# spi-interface.net
KiCad netlist of a schematic drawn in EAGLE
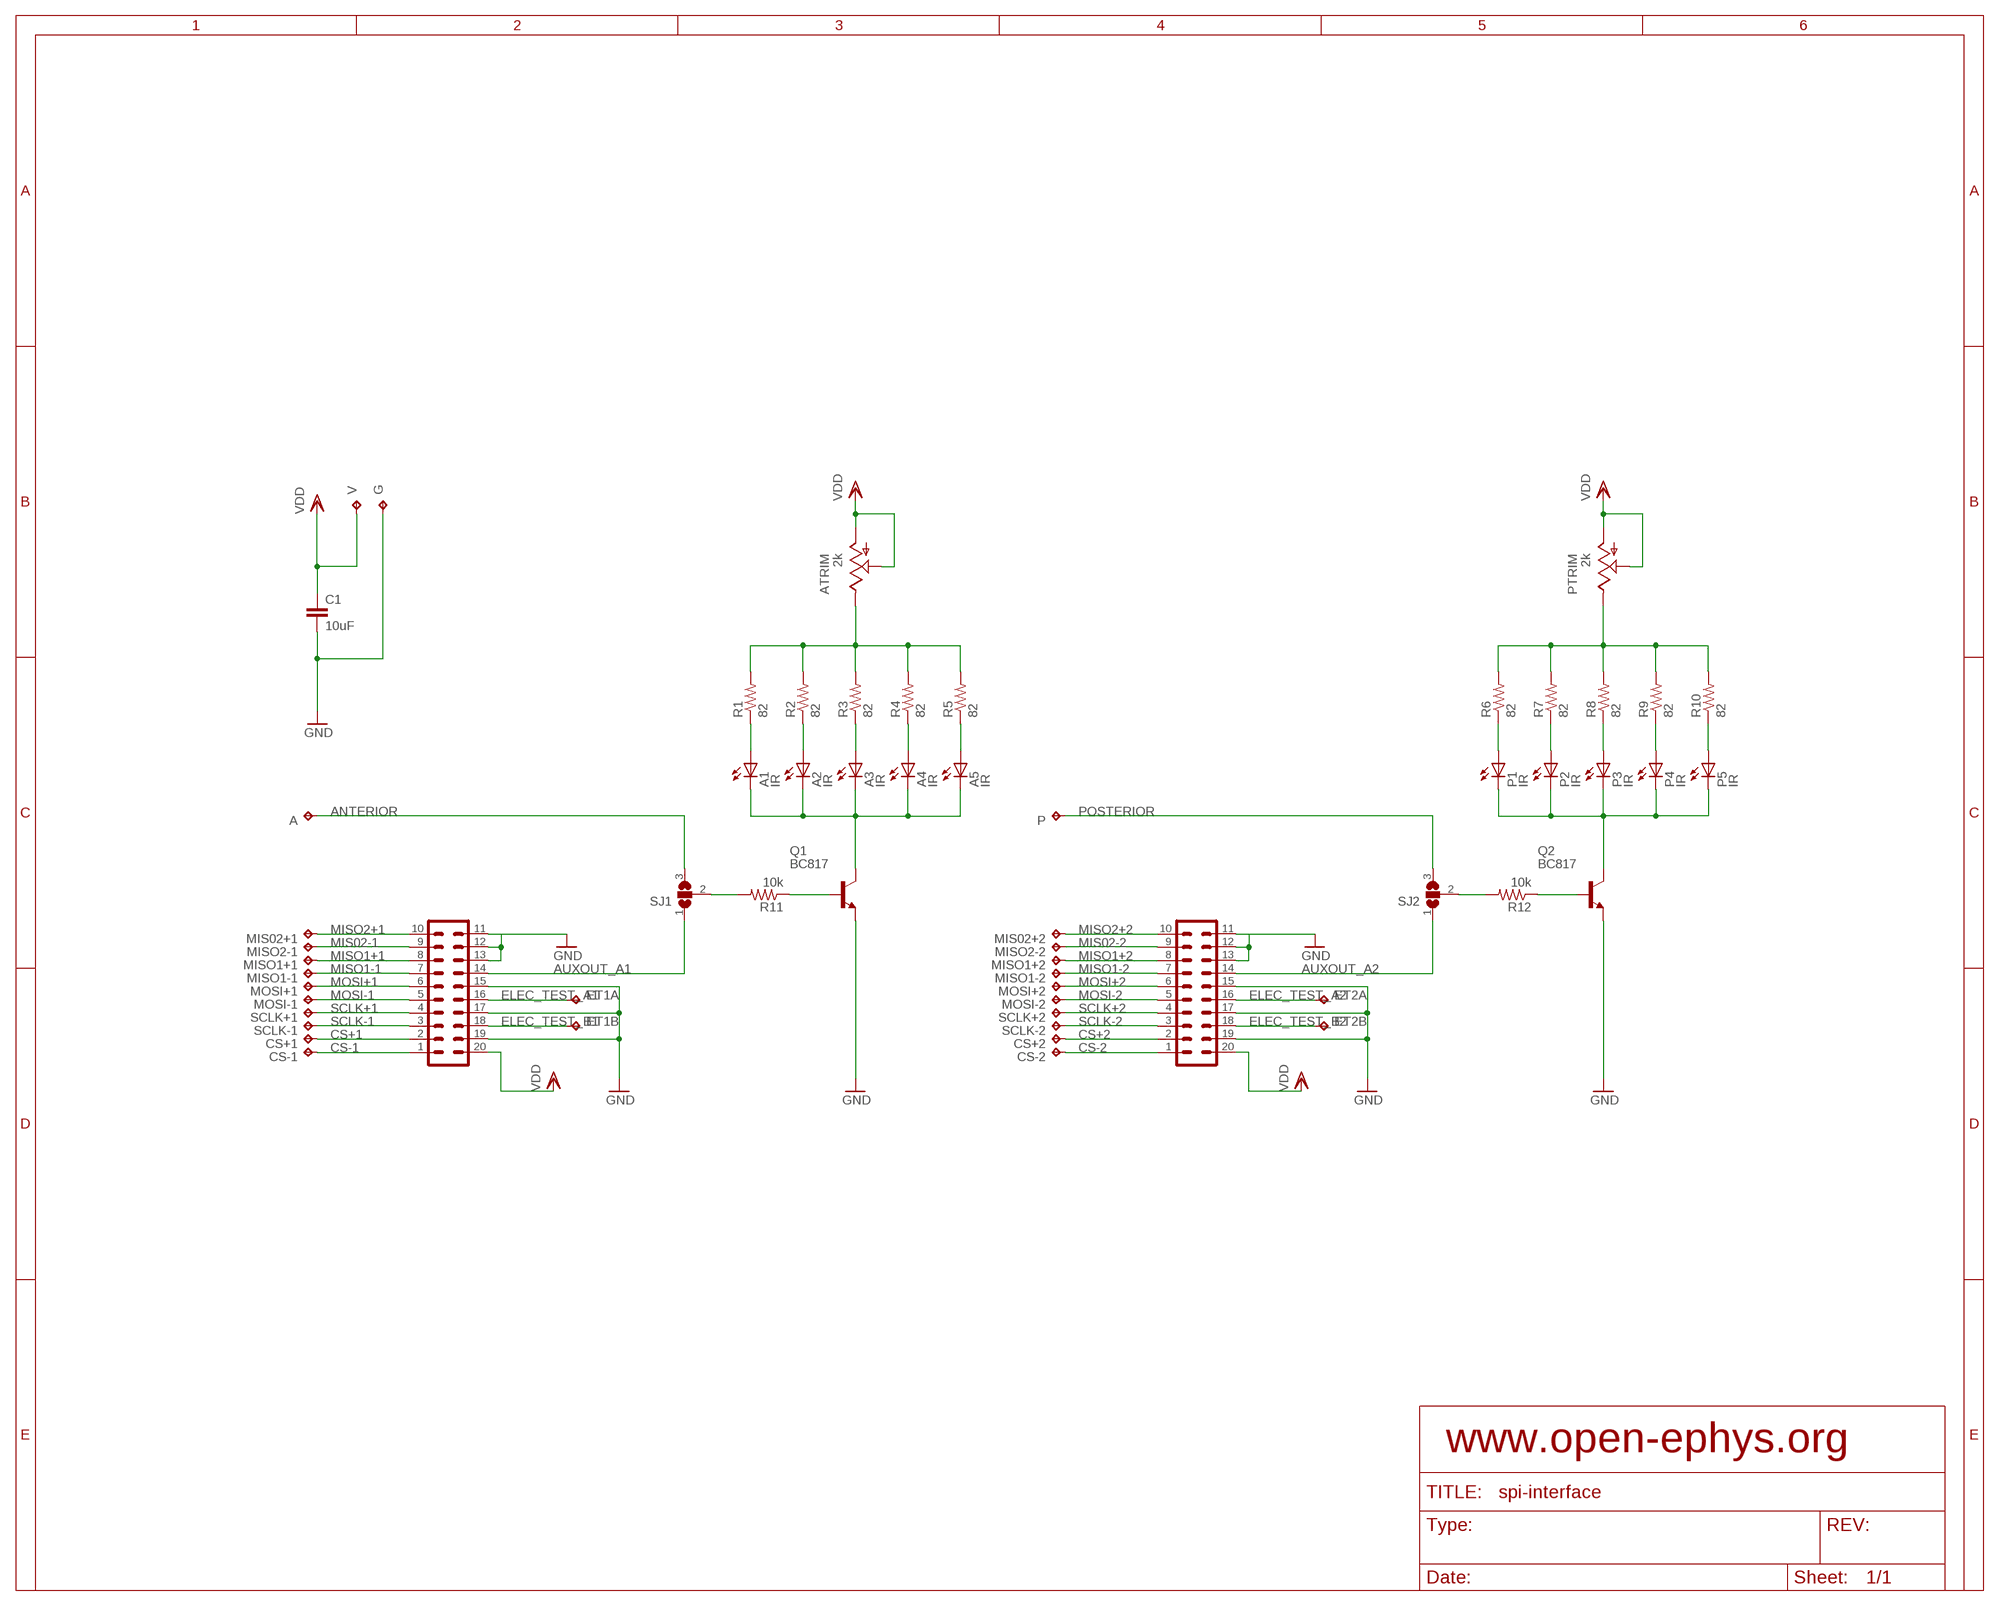
[diagram p0: schematic, sheet 1]

(export (version "E")
  (design (tool "Eeschema 10.0.6"))
  (components
    (comp (ref "A")
      (value "TP_01")
      (footprint "eagle-import:TP01")
      (libsource (lib "eagle-import") (part "TP_01"))
    )
    (comp (ref "A1")
      (value "IR")
      (footprint "eagle-import:LED-0603")
      (libsource (lib "eagle-import") (part "LED_0603"))
    )
    (comp (ref "A2")
      (value "IR")
      (footprint "eagle-import:LED-0603")
      (libsource (lib "eagle-import") (part "LED_0603"))
    )
    (comp (ref "A3")
      (value "IR")
      (footprint "eagle-import:LED-0603")
      (libsource (lib "eagle-import") (part "LED_0603"))
    )
    (comp (ref "A4")
      (value "IR")
      (footprint "eagle-import:LED-0603")
      (libsource (lib "eagle-import") (part "LED_0603"))
    )
    (comp (ref "A5")
      (value "IR")
      (footprint "eagle-import:LED-0603")
      (libsource (lib "eagle-import") (part "LED_0603"))
    )
    (comp (ref "ATRIM")
      (value "2k")
      (footprint "eagle-import:EIA_EIAJ")
      (libsource (lib "eagle-import") (part "TRIM_EIA/EIAJ"))
    )
    (comp (ref "C1")
      (value "10uF")
      (footprint "eagle-import:0805")
      (fields (field (name "PARTNO") "C2012X5R1Cxxxxxxx"))
      (libsource (lib "eagle-import") (part "C_0805"))
    )
    (comp (ref "CS+1")
      (value "TP_01")
      (footprint "eagle-import:TP01")
      (libsource (lib "eagle-import") (part "TP_01"))
    )
    (comp (ref "CS+2")
      (value "TP_01")
      (footprint "eagle-import:TP01")
      (libsource (lib "eagle-import") (part "TP_01"))
    )
    (comp (ref "CS-1")
      (value "TP_01")
      (footprint "eagle-import:TP01")
      (libsource (lib "eagle-import") (part "TP_01"))
    )
    (comp (ref "CS-2")
      (value "TP_01")
      (footprint "eagle-import:TP01")
      (libsource (lib "eagle-import") (part "TP_01"))
    )
    (comp (ref "ET1A")
      (value "TP_03")
      (footprint "eagle-import:TP03")
      (libsource (lib "eagle-import") (part "TP_03"))
    )
    (comp (ref "ET1B")
      (value "TP_03")
      (footprint "eagle-import:TP03")
      (libsource (lib "eagle-import") (part "TP_03"))
    )
    (comp (ref "ET2A")
      (value "TP_03")
      (footprint "eagle-import:TP03")
      (libsource (lib "eagle-import") (part "TP_03"))
    )
    (comp (ref "ET2B")
      (value "TP_03")
      (footprint "eagle-import:TP03")
      (libsource (lib "eagle-import") (part "TP_03"))
    )
    (comp (ref "G")
      (value "TP_02")
      (footprint "eagle-import:TP02")
      (libsource (lib "eagle-import") (part "TP_02"))
    )
    (comp (ref "HS1")
      (value "JMD20-V")
      (footprint "eagle-import:JMD20-V")
      (libsource (lib "eagle-import") (part "PINHD-2X10_JMD20-V"))
    )
    (comp (ref "HS2")
      (value "JMD20-V")
      (footprint "eagle-import:JMD20-V")
      (libsource (lib "eagle-import") (part "PINHD-2X10_JMD20-V"))
    )
    (comp (ref "MIS02+1")
      (value "TP_01")
      (footprint "eagle-import:TP01")
      (libsource (lib "eagle-import") (part "TP_01"))
    )
    (comp (ref "MIS02+2")
      (value "TP_01")
      (footprint "eagle-import:TP01")
      (libsource (lib "eagle-import") (part "TP_01"))
    )
    (comp (ref "MISO1+1")
      (value "TP_01")
      (footprint "eagle-import:TP01")
      (libsource (lib "eagle-import") (part "TP_01"))
    )
    (comp (ref "MISO1+2")
      (value "TP_01")
      (footprint "eagle-import:TP01")
      (libsource (lib "eagle-import") (part "TP_01"))
    )
    (comp (ref "MISO1-1")
      (value "TP_01")
      (footprint "eagle-import:TP01")
      (libsource (lib "eagle-import") (part "TP_01"))
    )
    (comp (ref "MISO1-2")
      (value "TP_01")
      (footprint "eagle-import:TP01")
      (libsource (lib "eagle-import") (part "TP_01"))
    )
    (comp (ref "MISO2-1")
      (value "TP_01")
      (footprint "eagle-import:TP01")
      (libsource (lib "eagle-import") (part "TP_01"))
    )
    (comp (ref "MISO2-2")
      (value "TP_01")
      (footprint "eagle-import:TP01")
      (libsource (lib "eagle-import") (part "TP_01"))
    )
    (comp (ref "MOSI+1")
      (value "TP_01")
      (footprint "eagle-import:TP01")
      (libsource (lib "eagle-import") (part "TP_01"))
    )
    (comp (ref "MOSI+2")
      (value "TP_01")
      (footprint "eagle-import:TP01")
      (libsource (lib "eagle-import") (part "TP_01"))
    )
    (comp (ref "MOSI-1")
      (value "TP_01")
      (footprint "eagle-import:TP01")
      (libsource (lib "eagle-import") (part "TP_01"))
    )
    (comp (ref "MOSI-2")
      (value "TP_01")
      (footprint "eagle-import:TP01")
      (libsource (lib "eagle-import") (part "TP_01"))
    )
    (comp (ref "P")
      (value "TP_01")
      (footprint "eagle-import:TP01")
      (libsource (lib "eagle-import") (part "TP_01"))
    )
    (comp (ref "P1")
      (value "IR")
      (footprint "eagle-import:LED-0603")
      (libsource (lib "eagle-import") (part "LED_0603"))
    )
    (comp (ref "P2")
      (value "IR")
      (footprint "eagle-import:LED-0603")
      (libsource (lib "eagle-import") (part "LED_0603"))
    )
    (comp (ref "P3")
      (value "IR")
      (footprint "eagle-import:LED-0603")
      (libsource (lib "eagle-import") (part "LED_0603"))
    )
    (comp (ref "P4")
      (value "IR")
      (footprint "eagle-import:LED-0603")
      (libsource (lib "eagle-import") (part "LED_0603"))
    )
    (comp (ref "P5")
      (value "IR")
      (footprint "eagle-import:LED-0603")
      (libsource (lib "eagle-import") (part "LED_0603"))
    )
    (comp (ref "PTRIM")
      (value "2k")
      (footprint "eagle-import:EIA_EIAJ")
      (libsource (lib "eagle-import") (part "TRIM_EIA/EIAJ"))
    )
    (comp (ref "Q1")
      (value "BC817")
      (footprint "eagle-import:SOT23-BEC")
      (libsource (lib "eagle-import") (part "BC817SMD-16"))
    )
    (comp (ref "Q2")
      (value "BC817")
      (footprint "eagle-import:SOT23-BEC")
      (libsource (lib "eagle-import") (part "BC817SMD-16"))
    )
    (comp (ref "R1")
      (value "82")
      (footprint "eagle-import:0402")
      (libsource (lib "eagle-import") (part "R_0402"))
    )
    (comp (ref "R2")
      (value "82")
      (footprint "eagle-import:0402")
      (libsource (lib "eagle-import") (part "R_0402"))
    )
    (comp (ref "R3")
      (value "82")
      (footprint "eagle-import:0402")
      (libsource (lib "eagle-import") (part "R_0402"))
    )
    (comp (ref "R4")
      (value "82")
      (footprint "eagle-import:0402")
      (libsource (lib "eagle-import") (part "R_0402"))
    )
    (comp (ref "R5")
      (value "82")
      (footprint "eagle-import:0402")
      (libsource (lib "eagle-import") (part "R_0402"))
    )
    (comp (ref "R6")
      (value "82")
      (footprint "eagle-import:0402")
      (libsource (lib "eagle-import") (part "R_0402"))
    )
    (comp (ref "R7")
      (value "82")
      (footprint "eagle-import:0402")
      (libsource (lib "eagle-import") (part "R_0402"))
    )
    (comp (ref "R8")
      (value "82")
      (footprint "eagle-import:0402")
      (libsource (lib "eagle-import") (part "R_0402"))
    )
    (comp (ref "R9")
      (value "82")
      (footprint "eagle-import:0402")
      (libsource (lib "eagle-import") (part "R_0402"))
    )
    (comp (ref "R10")
      (value "82")
      (footprint "eagle-import:0402")
      (libsource (lib "eagle-import") (part "R_0402"))
    )
    (comp (ref "R11")
      (value "10k")
      (footprint "eagle-import:0402")
      (libsource (lib "eagle-import") (part "R_0402"))
    )
    (comp (ref "R12")
      (value "10k")
      (footprint "eagle-import:0402")
      (libsource (lib "eagle-import") (part "R_0402"))
    )
    (comp (ref "SCLK+1")
      (value "TP_01")
      (footprint "eagle-import:TP01")
      (libsource (lib "eagle-import") (part "TP_01"))
    )
    (comp (ref "SCLK+2")
      (value "TP_01")
      (footprint "eagle-import:TP01")
      (libsource (lib "eagle-import") (part "TP_01"))
    )
    (comp (ref "SCLK-1")
      (value "TP_01")
      (footprint "eagle-import:TP01")
      (libsource (lib "eagle-import") (part "TP_01"))
    )
    (comp (ref "SCLK-2")
      (value "TP_01")
      (footprint "eagle-import:TP01")
      (libsource (lib "eagle-import") (part "TP_01"))
    )
    (comp (ref "SJ1")
      (value "SJ2W")
      (footprint "eagle-import:SJ_2")
      (libsource (lib "eagle-import") (part "SJ2W"))
    )
    (comp (ref "SJ2")
      (value "SJ2W")
      (footprint "eagle-import:SJ_2")
      (libsource (lib "eagle-import") (part "SJ2W"))
    )
    (comp (ref "V")
      (value "TP_02")
      (footprint "eagle-import:TP02")
      (libsource (lib "eagle-import") (part "TP_02"))
    )
  )
  (nets
    (net (code "1") (name "/ANTERIOR") (class "Default")
      (node (ref "A") (pin "TP") (pinfunction "TP_TP") (pintype "input"))
      (node (ref "SJ1") (pin "3") (pinfunction "3_3") (pintype "passive"))
    )
    (net (code "2") (name "/AUXOUT_A1") (class "Default")
      (node (ref "HS1") (pin "14") (pinfunction "14_14") (pintype "bidirectional"))
      (node (ref "SJ1") (pin "1") (pinfunction "1_1") (pintype "passive"))
    )
    (net (code "3") (name "/AUXOUT_A2") (class "Default")
      (node (ref "HS2") (pin "14") (pinfunction "14_14") (pintype "bidirectional"))
      (node (ref "SJ2") (pin "1") (pinfunction "1_1") (pintype "passive"))
    )
    (net (code "4") (name "/CS+1") (class "Default")
      (node (ref "CS+1") (pin "TP") (pinfunction "TP_TP") (pintype "input"))
      (node (ref "HS1") (pin "2") (pinfunction "2_2") (pintype "bidirectional"))
    )
    (net (code "5") (name "/CS+2") (class "Default")
      (node (ref "CS+2") (pin "TP") (pinfunction "TP_TP") (pintype "input"))
      (node (ref "HS2") (pin "2") (pinfunction "2_2") (pintype "bidirectional"))
    )
    (net (code "6") (name "/CS-1") (class "Default")
      (node (ref "CS-1") (pin "TP") (pinfunction "TP_TP") (pintype "input"))
      (node (ref "HS1") (pin "1") (pinfunction "1_1") (pintype "bidirectional"))
    )
    (net (code "7") (name "/CS-2") (class "Default")
      (node (ref "CS-2") (pin "TP") (pinfunction "TP_TP") (pintype "input"))
      (node (ref "HS2") (pin "1") (pinfunction "1_1") (pintype "bidirectional"))
    )
    (net (code "8") (name "/ELEC_TEST_A1") (class "Default")
      (node (ref "ET1A") (pin "TP") (pinfunction "TP_TP") (pintype "input"))
      (node (ref "HS1") (pin "16") (pinfunction "16_16") (pintype "bidirectional"))
    )
    (net (code "9") (name "/ELEC_TEST_A2") (class "Default")
      (node (ref "ET2A") (pin "TP") (pinfunction "TP_TP") (pintype "input"))
      (node (ref "HS2") (pin "16") (pinfunction "16_16") (pintype "bidirectional"))
    )
    (net (code "10") (name "/ELEC_TEST_B1") (class "Default")
      (node (ref "ET1B") (pin "TP") (pinfunction "TP_TP") (pintype "input"))
      (node (ref "HS1") (pin "18") (pinfunction "18_18") (pintype "bidirectional"))
    )
    (net (code "11") (name "/ELEC_TEST_B2") (class "Default")
      (node (ref "ET2B") (pin "TP") (pinfunction "TP_TP") (pintype "input"))
      (node (ref "HS2") (pin "18") (pinfunction "18_18") (pintype "bidirectional"))
    )
    (net (code "12") (name "/MIS02-1") (class "Default")
      (node (ref "HS1") (pin "9") (pinfunction "9_9") (pintype "bidirectional"))
      (node (ref "MISO2-1") (pin "TP") (pinfunction "TP_TP") (pintype "input"))
    )
    (net (code "13") (name "/MIS02-2") (class "Default")
      (node (ref "HS2") (pin "9") (pinfunction "9_9") (pintype "bidirectional"))
      (node (ref "MISO2-2") (pin "TP") (pinfunction "TP_TP") (pintype "input"))
    )
    (net (code "14") (name "/MISO1+1") (class "Default")
      (node (ref "HS1") (pin "8") (pinfunction "8_8") (pintype "bidirectional"))
      (node (ref "MISO1+1") (pin "TP") (pinfunction "TP_TP") (pintype "input"))
    )
    (net (code "15") (name "/MISO1+2") (class "Default")
      (node (ref "HS2") (pin "8") (pinfunction "8_8") (pintype "bidirectional"))
      (node (ref "MISO1+2") (pin "TP") (pinfunction "TP_TP") (pintype "input"))
    )
    (net (code "16") (name "/MISO1-1") (class "Default")
      (node (ref "HS1") (pin "7") (pinfunction "7_7") (pintype "bidirectional"))
      (node (ref "MISO1-1") (pin "TP") (pinfunction "TP_TP") (pintype "input"))
    )
    (net (code "17") (name "/MISO1-2") (class "Default")
      (node (ref "HS2") (pin "7") (pinfunction "7_7") (pintype "bidirectional"))
      (node (ref "MISO1-2") (pin "TP") (pinfunction "TP_TP") (pintype "input"))
    )
    (net (code "18") (name "/MISO2+1") (class "Default")
      (node (ref "HS1") (pin "10") (pinfunction "10_10") (pintype "bidirectional"))
      (node (ref "MIS02+1") (pin "TP") (pinfunction "TP_TP") (pintype "input"))
    )
    (net (code "19") (name "/MISO2+2") (class "Default")
      (node (ref "HS2") (pin "10") (pinfunction "10_10") (pintype "bidirectional"))
      (node (ref "MIS02+2") (pin "TP") (pinfunction "TP_TP") (pintype "input"))
    )
    (net (code "20") (name "/MOSI+1") (class "Default")
      (node (ref "HS1") (pin "6") (pinfunction "6_6") (pintype "bidirectional"))
      (node (ref "MOSI+1") (pin "TP") (pinfunction "TP_TP") (pintype "input"))
    )
    (net (code "21") (name "/MOSI+2") (class "Default")
      (node (ref "HS2") (pin "6") (pinfunction "6_6") (pintype "bidirectional"))
      (node (ref "MOSI+2") (pin "TP") (pinfunction "TP_TP") (pintype "input"))
    )
    (net (code "22") (name "/MOSI-1") (class "Default")
      (node (ref "HS1") (pin "5") (pinfunction "5_5") (pintype "bidirectional"))
      (node (ref "MOSI-1") (pin "TP") (pinfunction "TP_TP") (pintype "input"))
    )
    (net (code "23") (name "/MOSI-2") (class "Default")
      (node (ref "HS2") (pin "5") (pinfunction "5_5") (pintype "bidirectional"))
      (node (ref "MOSI-2") (pin "TP") (pinfunction "TP_TP") (pintype "input"))
    )
    (net (code "24") (name "/POSTERIOR") (class "Default")
      (node (ref "P") (pin "TP") (pinfunction "TP_TP") (pintype "input"))
      (node (ref "SJ2") (pin "3") (pinfunction "3_3") (pintype "passive"))
    )
    (net (code "25") (name "/SCLK+1") (class "Default")
      (node (ref "HS1") (pin "4") (pinfunction "4_4") (pintype "bidirectional"))
      (node (ref "SCLK+1") (pin "TP") (pinfunction "TP_TP") (pintype "input"))
    )
    (net (code "26") (name "/SCLK+2") (class "Default")
      (node (ref "HS2") (pin "4") (pinfunction "4_4") (pintype "bidirectional"))
      (node (ref "SCLK+2") (pin "TP") (pinfunction "TP_TP") (pintype "input"))
    )
    (net (code "27") (name "/SCLK-1") (class "Default")
      (node (ref "HS1") (pin "3") (pinfunction "3_3") (pintype "bidirectional"))
      (node (ref "SCLK-1") (pin "TP") (pinfunction "TP_TP") (pintype "input"))
    )
    (net (code "28") (name "/SCLK-2") (class "Default")
      (node (ref "HS2") (pin "3") (pinfunction "3_3") (pintype "bidirectional"))
      (node (ref "SCLK-2") (pin "TP") (pinfunction "TP_TP") (pintype "input"))
    )
    (net (code "29") (name "GND") (class "Default")
      (node (ref "C1") (pin "2") (pinfunction "2_2") (pintype "passive"))
      (node (ref "G") (pin "TP") (pinfunction "TP_TP") (pintype "input"))
      (node (ref "HS1") (pin "11") (pinfunction "11_11") (pintype "bidirectional"))
      (node (ref "HS1") (pin "12") (pinfunction "12_12") (pintype "bidirectional"))
      (node (ref "HS1") (pin "13") (pinfunction "13_13") (pintype "bidirectional"))
      (node (ref "HS1") (pin "15") (pinfunction "15_15") (pintype "bidirectional"))
      (node (ref "HS1") (pin "17") (pinfunction "17_17") (pintype "bidirectional"))
      (node (ref "HS1") (pin "19") (pinfunction "19_19") (pintype "bidirectional"))
      (node (ref "HS2") (pin "11") (pinfunction "11_11") (pintype "bidirectional"))
      (node (ref "HS2") (pin "12") (pinfunction "12_12") (pintype "bidirectional"))
      (node (ref "HS2") (pin "13") (pinfunction "13_13") (pintype "bidirectional"))
      (node (ref "HS2") (pin "15") (pinfunction "15_15") (pintype "bidirectional"))
      (node (ref "HS2") (pin "17") (pinfunction "17_17") (pintype "bidirectional"))
      (node (ref "HS2") (pin "19") (pinfunction "19_19") (pintype "bidirectional"))
      (node (ref "Q1") (pin "E") (pinfunction "E_E") (pintype "passive"))
      (node (ref "Q2") (pin "E") (pinfunction "E_E") (pintype "passive"))
    )
    (net (code "30") (name "Net-(A1-PadA)") (class "Default")
      (node (ref "A1") (pin "A") (pinfunction "A_A") (pintype "passive"))
      (node (ref "R1") (pin "1") (pinfunction "1_1") (pintype "passive"))
    )
    (net (code "31") (name "Net-(A1-PadC)") (class "Default")
      (node (ref "A1") (pin "C") (pinfunction "C_C") (pintype "passive"))
      (node (ref "A2") (pin "C") (pinfunction "C_C") (pintype "passive"))
      (node (ref "A3") (pin "C") (pinfunction "C_C") (pintype "passive"))
      (node (ref "A4") (pin "C") (pinfunction "C_C") (pintype "passive"))
      (node (ref "A5") (pin "C") (pinfunction "C_C") (pintype "passive"))
      (node (ref "Q1") (pin "C") (pinfunction "C_C") (pintype "passive"))
    )
    (net (code "32") (name "Net-(A2-PadA)") (class "Default")
      (node (ref "A2") (pin "A") (pinfunction "A_A") (pintype "passive"))
      (node (ref "R2") (pin "1") (pinfunction "1_1") (pintype "passive"))
    )
    (net (code "33") (name "Net-(A3-PadA)") (class "Default")
      (node (ref "A3") (pin "A") (pinfunction "A_A") (pintype "passive"))
      (node (ref "R3") (pin "1") (pinfunction "1_1") (pintype "passive"))
    )
    (net (code "34") (name "Net-(A4-PadA)") (class "Default")
      (node (ref "A4") (pin "A") (pinfunction "A_A") (pintype "passive"))
      (node (ref "R4") (pin "1") (pinfunction "1_1") (pintype "passive"))
    )
    (net (code "35") (name "Net-(A5-PadA)") (class "Default")
      (node (ref "A5") (pin "A") (pinfunction "A_A") (pintype "passive"))
      (node (ref "R5") (pin "1") (pinfunction "1_1") (pintype "passive"))
    )
    (net (code "36") (name "Net-(ATRIM-PadE)") (class "Default")
      (node (ref "ATRIM") (pin "E") (pinfunction "E_E") (pintype "passive"))
      (node (ref "R1") (pin "2") (pinfunction "2_2") (pintype "passive"))
      (node (ref "R2") (pin "2") (pinfunction "2_2") (pintype "passive"))
      (node (ref "R3") (pin "2") (pinfunction "2_2") (pintype "passive"))
      (node (ref "R4") (pin "2") (pinfunction "2_2") (pintype "passive"))
      (node (ref "R5") (pin "2") (pinfunction "2_2") (pintype "passive"))
    )
    (net (code "37") (name "Net-(P1-PadA)") (class "Default")
      (node (ref "P1") (pin "A") (pinfunction "A_A") (pintype "passive"))
      (node (ref "R6") (pin "1") (pinfunction "1_1") (pintype "passive"))
    )
    (net (code "38") (name "Net-(P1-PadC)") (class "Default")
      (node (ref "P1") (pin "C") (pinfunction "C_C") (pintype "passive"))
      (node (ref "P2") (pin "C") (pinfunction "C_C") (pintype "passive"))
      (node (ref "P3") (pin "C") (pinfunction "C_C") (pintype "passive"))
      (node (ref "P4") (pin "C") (pinfunction "C_C") (pintype "passive"))
      (node (ref "P5") (pin "C") (pinfunction "C_C") (pintype "passive"))
      (node (ref "Q2") (pin "C") (pinfunction "C_C") (pintype "passive"))
    )
    (net (code "39") (name "Net-(P2-PadA)") (class "Default")
      (node (ref "P2") (pin "A") (pinfunction "A_A") (pintype "passive"))
      (node (ref "R7") (pin "1") (pinfunction "1_1") (pintype "passive"))
    )
    (net (code "40") (name "Net-(P3-PadA)") (class "Default")
      (node (ref "P3") (pin "A") (pinfunction "A_A") (pintype "passive"))
      (node (ref "R8") (pin "1") (pinfunction "1_1") (pintype "passive"))
    )
    (net (code "41") (name "Net-(P4-PadA)") (class "Default")
      (node (ref "P4") (pin "A") (pinfunction "A_A") (pintype "passive"))
      (node (ref "R9") (pin "1") (pinfunction "1_1") (pintype "passive"))
    )
    (net (code "42") (name "Net-(P5-PadA)") (class "Default")
      (node (ref "P5") (pin "A") (pinfunction "A_A") (pintype "passive"))
      (node (ref "R10") (pin "1") (pinfunction "1_1") (pintype "passive"))
    )
    (net (code "43") (name "Net-(PTRIM-PadE)") (class "Default")
      (node (ref "PTRIM") (pin "E") (pinfunction "E_E") (pintype "passive"))
      (node (ref "R10") (pin "2") (pinfunction "2_2") (pintype "passive"))
      (node (ref "R6") (pin "2") (pinfunction "2_2") (pintype "passive"))
      (node (ref "R7") (pin "2") (pinfunction "2_2") (pintype "passive"))
      (node (ref "R8") (pin "2") (pinfunction "2_2") (pintype "passive"))
      (node (ref "R9") (pin "2") (pinfunction "2_2") (pintype "passive"))
    )
    (net (code "44") (name "Net-(Q1-PadB)") (class "Default")
      (node (ref "Q1") (pin "B") (pinfunction "B_B") (pintype "passive"))
      (node (ref "R11") (pin "1") (pinfunction "1_1") (pintype "passive"))
    )
    (net (code "45") (name "Net-(Q2-PadB)") (class "Default")
      (node (ref "Q2") (pin "B") (pinfunction "B_B") (pintype "passive"))
      (node (ref "R12") (pin "1") (pinfunction "1_1") (pintype "passive"))
    )
    (net (code "46") (name "Net-(R11-Pad2)") (class "Default")
      (node (ref "R11") (pin "2") (pinfunction "2_2") (pintype "passive"))
      (node (ref "SJ1") (pin "2") (pinfunction "2_2") (pintype "passive"))
    )
    (net (code "47") (name "Net-(R12-Pad2)") (class "Default")
      (node (ref "R12") (pin "2") (pinfunction "2_2") (pintype "passive"))
      (node (ref "SJ2") (pin "2") (pinfunction "2_2") (pintype "passive"))
    )
    (net (code "48") (name "VDD") (class "Default")
      (node (ref "ATRIM") (pin "A") (pinfunction "A_A") (pintype "passive"))
      (node (ref "ATRIM") (pin "S") (pinfunction "S_S") (pintype "passive"))
      (node (ref "C1") (pin "1") (pinfunction "1_1") (pintype "passive"))
      (node (ref "HS1") (pin "20") (pinfunction "20_20") (pintype "bidirectional"))
      (node (ref "HS2") (pin "20") (pinfunction "20_20") (pintype "bidirectional"))
      (node (ref "PTRIM") (pin "A") (pinfunction "A_A") (pintype "passive"))
      (node (ref "PTRIM") (pin "S") (pinfunction "S_S") (pintype "passive"))
      (node (ref "V") (pin "TP") (pinfunction "TP_TP") (pintype "input"))
    )
  )
)
